# 24V_LM7824.net
KiCad netlist of a schematic drawn in EAGLE
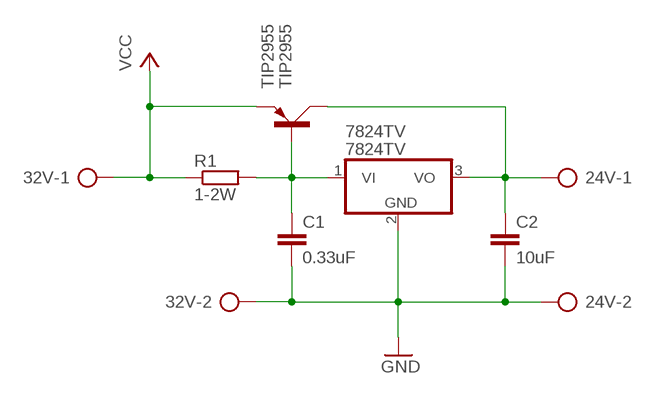
[diagram p0: schematic, sheet 1]

(export (version "E")
  (design (tool "Eeschema 10.0.6"))
  (components
    (comp (ref "24V")
      (value "SMKDSP_1,5/2")
      (footprint "eagle-import:SMKDSP_1,5_2")
      (fields (field (name "MF") "FARNELL") (field (name "MPN") "1733570"))
      (libsource (lib "eagle-import") (part "SMKDSP_1,5/2"))
    )
    (comp (ref "32V")
      (value "SMKDSP_1,5/2")
      (footprint "eagle-import:SMKDSP_1,5_2")
      (fields (field (name "MF") "FARNELL") (field (name "MPN") "1733570"))
      (libsource (lib "eagle-import") (part "SMKDSP_1,5/2"))
    )
    (comp (ref "7824TV")
      (value "7824TV")
      (footprint "eagle-import:TO220V")
      (libsource (lib "eagle-import") (part "78TV24"))
    )
    (comp (ref "C1")
      (value "0.33uF")
      (footprint "eagle-import:C025-025X050")
      (libsource (lib "eagle-import") (part "C-EU025-025X050"))
    )
    (comp (ref "C2")
      (value "10uF")
      (footprint "eagle-import:C025-025X050")
      (libsource (lib "eagle-import") (part "C-EU025-025X050"))
    )
    (comp (ref "R1")
      (value "1-2W")
      (footprint "eagle-import:0309_10")
      (libsource (lib "eagle-import") (part "R-EU_0309/10"))
    )
    (comp (ref "TIP2955")
      (value "TIP2955")
      (footprint "eagle-import:TOP3AV")
      (libsource (lib "eagle-import") (part "TIP2955"))
    )
  )
  (nets
    (net (code "1") (name "GND") (class "Default")
      (node (ref "24V") (pin "2") (pinfunction "KL_2") (pintype "passive"))
      (node (ref "32V") (pin "2") (pinfunction "KL_2") (pintype "passive"))
      (node (ref "7824TV") (pin "2") (pinfunction "GND_2") (pintype "passive"))
      (node (ref "C1") (pin "2") (pinfunction "2_2") (pintype "passive"))
      (node (ref "C2") (pin "2") (pinfunction "2_2") (pintype "passive"))
    )
    (net (code "2") (name "Net-(24VA-KL)") (class "Default")
      (node (ref "24V") (pin "1") (pinfunction "KL_1") (pintype "passive"))
      (node (ref "7824TV") (pin "3") (pinfunction "VO_3") (pintype "passive"))
      (node (ref "C2") (pin "1") (pinfunction "1_1") (pintype "passive"))
      (node (ref "TIP2955") (pin "C") (pinfunction "C_C") (pintype "passive"))
    )
    (net (code "3") (name "Net-(7824TV-VI)") (class "Default")
      (node (ref "7824TV") (pin "1") (pinfunction "VI_1") (pintype "input"))
      (node (ref "C1") (pin "1") (pinfunction "1_1") (pintype "passive"))
      (node (ref "R1") (pin "2") (pinfunction "2_2") (pintype "passive"))
      (node (ref "TIP2955") (pin "B") (pinfunction "B_B") (pintype "passive"))
    )
    (net (code "4") (name "VCC") (class "Default")
      (node (ref "32V") (pin "1") (pinfunction "KL_1") (pintype "passive"))
      (node (ref "R1") (pin "1") (pinfunction "1_1") (pintype "passive"))
      (node (ref "TIP2955") (pin "E") (pinfunction "E_E") (pintype "passive"))
    )
  )
)
